# AND_D001A.net
KiCad netlist of a schematic drawn in EAGLE
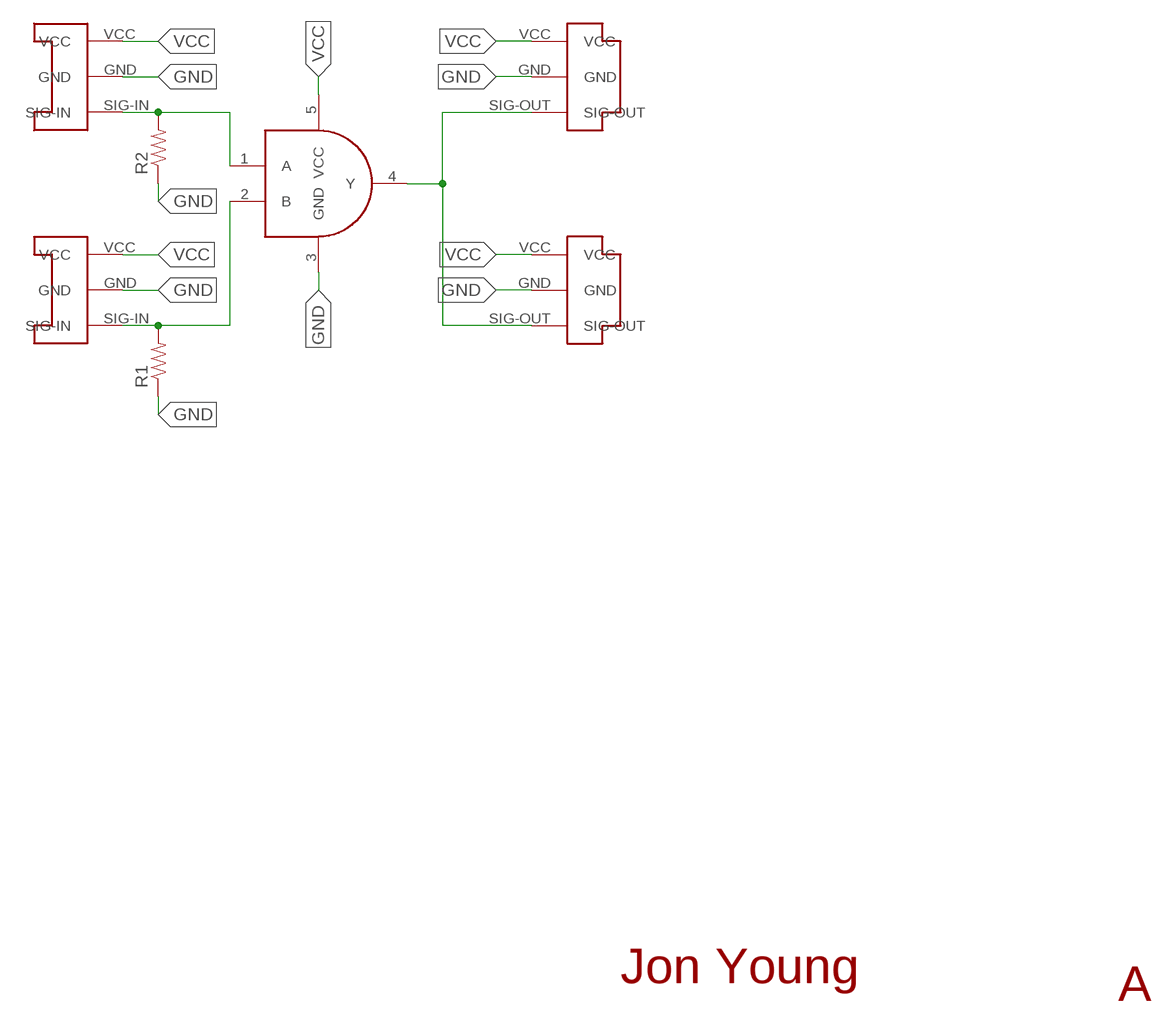
[diagram p0: schematic, sheet 1]

(export (version "E")
  (design (tool "Eeschema 10.0.6"))
  (components
    (comp (ref "R1")
      (value "RESISTOR0603")
      (footprint "eagle-import:0603-RES")
      (libsource (lib "eagle-import") (part "RESISTOR0603"))
    )
    (comp (ref "R2")
      (value "RESISTOR0603")
      (footprint "eagle-import:0603-RES")
      (libsource (lib "eagle-import") (part "RESISTOR0603"))
    )
    (comp (ref "U$1")
      (value "CONN-PLUG-3POS-3MM")
      (footprint "eagle-import:PLUG-3POS-3MM-SMD")
      (libsource (lib "eagle-import") (part "CONN-PLUG-3POS-3MM"))
    )
    (comp (ref "U$2")
      (value "CONN-SOCKET-3POS-3MM")
      (footprint "eagle-import:SOCKET-3POS-3MM-SMD")
      (libsource (lib "eagle-import") (part "CONN-SOCKET-3POS-3MM"))
    )
    (comp (ref "U$3")
      (value "CONN-SOCKET-3POS-3MM")
      (footprint "eagle-import:SOCKET-3POS-3MM-SMD")
      (libsource (lib "eagle-import") (part "CONN-SOCKET-3POS-3MM"))
    )
    (comp (ref "U$4")
      (value "CONN-PLUG-3POS-3MM")
      (footprint "eagle-import:PLUG-3POS-3MM-SMD")
      (libsource (lib "eagle-import") (part "CONN-PLUG-3POS-3MM"))
    )
    (comp (ref "U$5")
      (value "AND-NC7SZ08")
      (footprint "eagle-import:SC70")
      (libsource (lib "eagle-import") (part "AND-NC7SZ08"))
    )
  )
  (nets
    (net (code "1") (name "GND") (class "Default")
      (node (ref "R1") (pin "1") (pinfunction "1_1") (pintype "passive"))
      (node (ref "R2") (pin "1") (pinfunction "1_1") (pintype "passive"))
      (node (ref "U$1") (pin "GND") (pinfunction "GND_GND") (pintype "power_in"))
      (node (ref "U$2") (pin "GND") (pinfunction "GND_GND") (pintype "power_in"))
      (node (ref "U$3") (pin "GND") (pinfunction "GND_GND") (pintype "power_in"))
      (node (ref "U$4") (pin "GND") (pinfunction "GND_GND") (pintype "power_in"))
      (node (ref "U$5") (pin "3") (pinfunction "GND_3") (pintype "power_in"))
    )
    (net (code "2") (name "Net-(U$5-A)") (class "Default")
      (node (ref "R2") (pin "2") (pinfunction "2_2") (pintype "passive"))
      (node (ref "U$3") (pin "SIG-IN") (pinfunction "SIG-IN_SIG-IN") (pintype "bidirectional"))
      (node (ref "U$5") (pin "1") (pinfunction "A_1") (pintype "input"))
    )
    (net (code "3") (name "Net-(U$5-B)") (class "Default")
      (node (ref "R1") (pin "2") (pinfunction "2_2") (pintype "passive"))
      (node (ref "U$2") (pin "SIG-IN") (pinfunction "SIG-IN_SIG-IN") (pintype "bidirectional"))
      (node (ref "U$5") (pin "2") (pinfunction "B_2") (pintype "input"))
    )
    (net (code "4") (name "Net-(U$5-Y)") (class "Default")
      (node (ref "U$1") (pin "SIG-OUT") (pinfunction "SIG-OUT_SIG-OUT") (pintype "bidirectional"))
      (node (ref "U$4") (pin "SIG-OUT") (pinfunction "SIG-OUT_SIG-OUT") (pintype "bidirectional"))
      (node (ref "U$5") (pin "4") (pinfunction "Y_4") (pintype "output"))
    )
    (net (code "5") (name "VCC") (class "Default")
      (node (ref "U$1") (pin "VCC") (pinfunction "VCC_VCC") (pintype "power_in"))
      (node (ref "U$2") (pin "VCC") (pinfunction "VCC_VCC") (pintype "power_in"))
      (node (ref "U$3") (pin "VCC") (pinfunction "VCC_VCC") (pintype "power_in"))
      (node (ref "U$4") (pin "VCC") (pinfunction "VCC_VCC") (pintype "power_in"))
      (node (ref "U$5") (pin "5") (pinfunction "VCC_5") (pintype "power_in"))
    )
  )
)
